# Accelerometer.net
KiCad netlist of a schematic drawn in Altium Designer
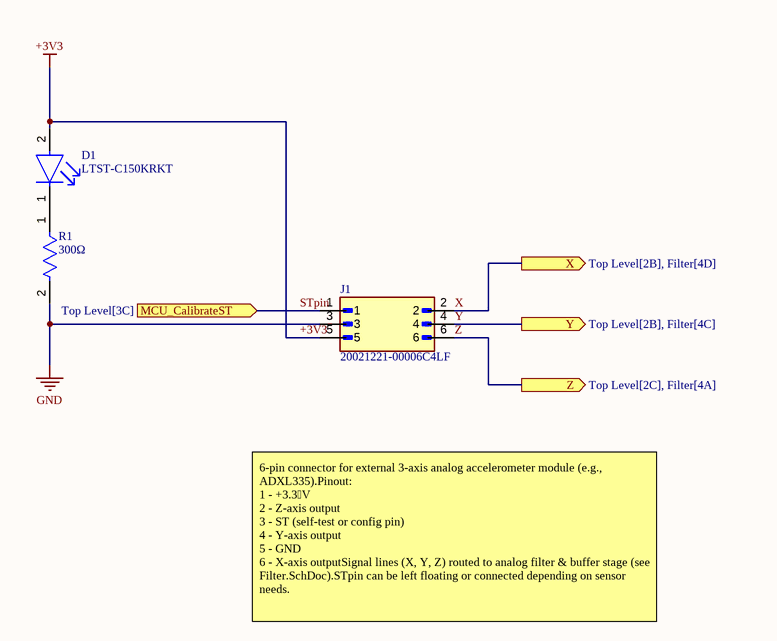
[diagram p0: Accelerometer.SchDoc]

(export (version "E")
  (design (tool "Eeschema 10.0.6"))
  (components
    (comp (ref "D1")
      (value "LTST-C150KRKT")
      (footprint "FP-LTST-C150KRKT-MFG")
      (description "LED RED CLEAR 1206 SMD")
      (libsource (lib "Altium Content Vault") (part "8706943c75ba83719d021d2fdc84c58"))
    )
    (comp (ref "J1")
      (value "20021221-00006C4LF")
      (footprint "AMPHENOL_20021221-00006C4LF")
      (fields (field (name "MF") "Amphenol ICC"))
      (libsource (lib "20021221-00006C4LF") (part "20021221-00006C4LF"))
    )
    (comp (ref "R1")
      (value "300Ω")
      (footprint "FP-RMCF0805-IPC_B")
      (description "300Ω ±5% 0.125W 0805 Thick Film Chip Resistor AEC-Q200 compliant, RMCF0805JT300R")
      (fields (field (name "TOLERANCE") "5%"))
      (libsource (lib "Altium Content Vault") (part "1029c3af85768c4190bb7ad29bc67b5"))
    )
  )
  (nets
    (net (code "1") (name "+3V3") (class "Default")
      (node (ref "D1") (pin "2") (pinfunction "A_2") (pintype "passive"))
      (node (ref "J1") (pin "5") (pinfunction "5_5") (pintype "passive"))
    )
    (net (code "2") (name "/STpin") (class "Default")
      (node (ref "J1") (pin "1") (pinfunction "1_1") (pintype "passive"))
    )
    (net (code "3") (name "/X") (class "Default")
      (node (ref "J1") (pin "2") (pinfunction "2_2") (pintype "passive"))
    )
    (net (code "4") (name "/Y") (class "Default")
      (node (ref "J1") (pin "4") (pinfunction "4_4") (pintype "passive"))
    )
    (net (code "5") (name "/Z") (class "Default")
      (node (ref "J1") (pin "6") (pinfunction "6_6") (pintype "passive"))
    )
    (net (code "6") (name "GND") (class "Default")
      (node (ref "J1") (pin "3") (pinfunction "3_3") (pintype "passive"))
      (node (ref "R1") (pin "2") (pinfunction "2_2") (pintype "passive"))
    )
    (net (code "7") (name "Net-(D1-C)") (class "Default")
      (node (ref "D1") (pin "1") (pinfunction "C_1") (pintype "passive"))
      (node (ref "R1") (pin "1") (pinfunction "1_1") (pintype "passive"))
    )
  )
)
